# MCU.net
KiCad netlist of a schematic drawn in Altium Designer
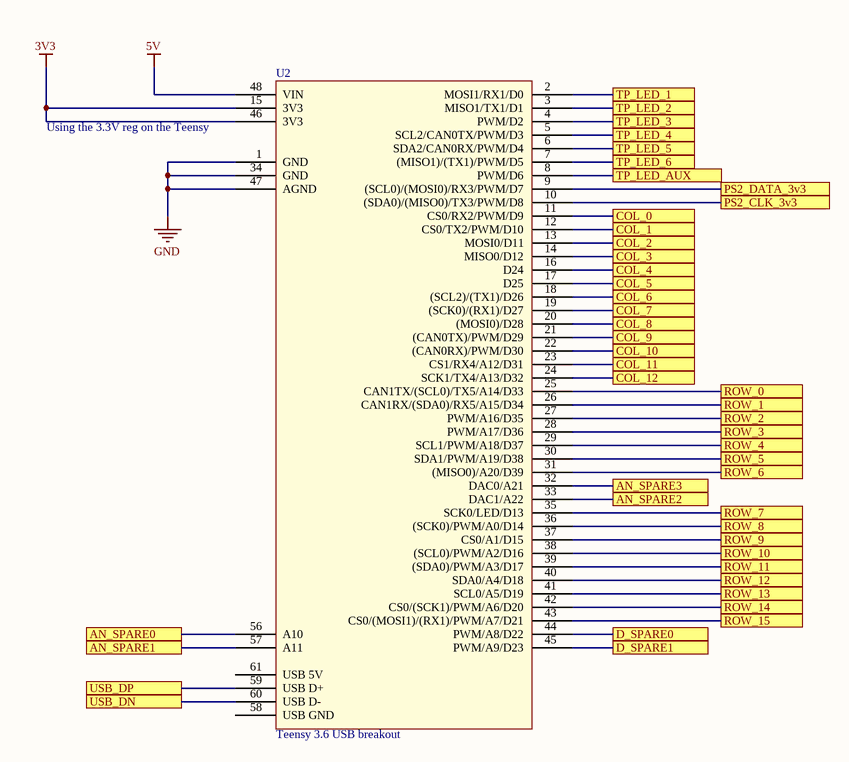
[diagram p0: MCU.SchDoc]

(export (version "E")
  (design (tool "Eeschema 10.0.6"))
  (components
    (comp (ref "U2")
      (value "Teensy 3.6 USB breakout")
      (footprint "Teensy 3.6 - USB Breakout")
      (libsource (lib "KBuchka-IntLib") (part "Teensy 3.6 USB breakout"))
    )
  )
  (nets
    (net (code "1") (name "/AN_SPARE0") (class "Default")
      (node (ref "U2") (pin "56") (pinfunction "A10_56") (pintype "passive"))
    )
    (net (code "2") (name "/AN_SPARE1") (class "Default")
      (node (ref "U2") (pin "57") (pinfunction "A11_57") (pintype "passive"))
    )
    (net (code "3") (name "/AN_SPARE2") (class "Default")
      (node (ref "U2") (pin "33") (pinfunction "DAC1/A22_33") (pintype "passive"))
    )
    (net (code "4") (name "/AN_SPARE3") (class "Default")
      (node (ref "U2") (pin "32") (pinfunction "DAC0/A21_32") (pintype "passive"))
    )
    (net (code "5") (name "/COL_0") (class "Default")
      (node (ref "U2") (pin "11") (pinfunction "CS0/RX2/PWM/D9_11") (pintype "passive"))
    )
    (net (code "6") (name "/COL_1") (class "Default")
      (node (ref "U2") (pin "12") (pinfunction "CS0/TX2/PWM/D10_12") (pintype "passive"))
    )
    (net (code "7") (name "/COL_2") (class "Default")
      (node (ref "U2") (pin "13") (pinfunction "MOSI0/D11_13") (pintype "passive"))
    )
    (net (code "8") (name "/COL_3") (class "Default")
      (node (ref "U2") (pin "14") (pinfunction "MISO0/D12_14") (pintype "passive"))
    )
    (net (code "9") (name "/COL_4") (class "Default")
      (node (ref "U2") (pin "16") (pinfunction "D24_16") (pintype "passive"))
    )
    (net (code "10") (name "/COL_5") (class "Default")
      (node (ref "U2") (pin "17") (pinfunction "D25_17") (pintype "passive"))
    )
    (net (code "11") (name "/COL_6") (class "Default")
      (node (ref "U2") (pin "18") (pinfunction "(SCL2)/(TX1)/D26_18") (pintype "passive"))
    )
    (net (code "12") (name "/COL_7") (class "Default")
      (node (ref "U2") (pin "19") (pinfunction "(SCK0)/(RX1)/D27_19") (pintype "passive"))
    )
    (net (code "13") (name "/COL_8") (class "Default")
      (node (ref "U2") (pin "20") (pinfunction "(MOSI0)/D28_20") (pintype "passive"))
    )
    (net (code "14") (name "/COL_9") (class "Default")
      (node (ref "U2") (pin "21") (pinfunction "(CAN0TX)/PWM/D29_21") (pintype "passive"))
    )
    (net (code "15") (name "/COL_10") (class "Default")
      (node (ref "U2") (pin "22") (pinfunction "(CAN0RX)/PWM/D30_22") (pintype "passive"))
    )
    (net (code "16") (name "/COL_11") (class "Default")
      (node (ref "U2") (pin "23") (pinfunction "CS1/RX4/A12/D31_23") (pintype "passive"))
    )
    (net (code "17") (name "/COL_12") (class "Default")
      (node (ref "U2") (pin "24") (pinfunction "SCK1/TX4/A13/D32_24") (pintype "passive"))
    )
    (net (code "18") (name "/D_SPARE0") (class "Default")
      (node (ref "U2") (pin "44") (pinfunction "PWM/A8/D22_44") (pintype "passive"))
    )
    (net (code "19") (name "/D_SPARE1") (class "Default")
      (node (ref "U2") (pin "45") (pinfunction "PWM/A9/D23_45") (pintype "passive"))
    )
    (net (code "20") (name "/PS2_CLK_3v3") (class "Default")
      (node (ref "U2") (pin "10") (pinfunction "(SDA0)/(MISO0)/TX3/PWM/D8_10") (pintype "passive"))
    )
    (net (code "21") (name "/PS2_DATA_3v3") (class "Default")
      (node (ref "U2") (pin "9") (pinfunction "(SCL0)/(MOSI0)/RX3/PWM/D7_9") (pintype "passive"))
    )
    (net (code "22") (name "/ROW_0") (class "Default")
      (node (ref "U2") (pin "25") (pinfunction "CAN1TX/(SCL0)/TX5/A14/D33_25") (pintype "passive"))
    )
    (net (code "23") (name "/ROW_1") (class "Default")
      (node (ref "U2") (pin "26") (pinfunction "CAN1RX/(SDA0)/RX5/A15/D34_26") (pintype "passive"))
    )
    (net (code "24") (name "/ROW_2") (class "Default")
      (node (ref "U2") (pin "27") (pinfunction "PWM/A16/D35_27") (pintype "passive"))
    )
    (net (code "25") (name "/ROW_3") (class "Default")
      (node (ref "U2") (pin "28") (pinfunction "PWM/A17/D36_28") (pintype "passive"))
    )
    (net (code "26") (name "/ROW_4") (class "Default")
      (node (ref "U2") (pin "29") (pinfunction "SCL1/PWM/A18/D37_29") (pintype "passive"))
    )
    (net (code "27") (name "/ROW_5") (class "Default")
      (node (ref "U2") (pin "30") (pinfunction "SDA1/PWM/A19/D38_30") (pintype "passive"))
    )
    (net (code "28") (name "/ROW_6") (class "Default")
      (node (ref "U2") (pin "31") (pinfunction "(MISO0)/A20/D39_31") (pintype "passive"))
    )
    (net (code "29") (name "/ROW_7") (class "Default")
      (node (ref "U2") (pin "35") (pinfunction "SCK0/LED/D13_35") (pintype "passive"))
    )
    (net (code "30") (name "/ROW_8") (class "Default")
      (node (ref "U2") (pin "36") (pinfunction "(SCK0)/PWM/A0/D14_36") (pintype "passive"))
    )
    (net (code "31") (name "/ROW_9") (class "Default")
      (node (ref "U2") (pin "37") (pinfunction "CS0/A1/D15_37") (pintype "passive"))
    )
    (net (code "32") (name "/ROW_10") (class "Default")
      (node (ref "U2") (pin "38") (pinfunction "(SCL0)/PWM/A2/D16_38") (pintype "passive"))
    )
    (net (code "33") (name "/ROW_11") (class "Default")
      (node (ref "U2") (pin "39") (pinfunction "(SDA0)/PWM/A3/D17_39") (pintype "passive"))
    )
    (net (code "34") (name "/ROW_12") (class "Default")
      (node (ref "U2") (pin "40") (pinfunction "SDA0/A4/D18_40") (pintype "passive"))
    )
    (net (code "35") (name "/ROW_13") (class "Default")
      (node (ref "U2") (pin "41") (pinfunction "SCL0/A5/D19_41") (pintype "passive"))
    )
    (net (code "36") (name "/ROW_14") (class "Default")
      (node (ref "U2") (pin "42") (pinfunction "CS0/(SCK1)/PWM/A6/D20_42") (pintype "passive"))
    )
    (net (code "37") (name "/ROW_15") (class "Default")
      (node (ref "U2") (pin "43") (pinfunction "CS0/(MOSI1)/(RX1)/PWM/A7/D21_43") (pintype "passive"))
    )
    (net (code "38") (name "/TP_LED_1") (class "Default")
      (node (ref "U2") (pin "2") (pinfunction "MOSI1/RX1/D0_2") (pintype "passive"))
    )
    (net (code "39") (name "/TP_LED_2") (class "Default")
      (node (ref "U2") (pin "3") (pinfunction "MISO1/TX1/D1_3") (pintype "passive"))
    )
    (net (code "40") (name "/TP_LED_3") (class "Default")
      (node (ref "U2") (pin "4") (pinfunction "PWM/D2_4") (pintype "passive"))
    )
    (net (code "41") (name "/TP_LED_4") (class "Default")
      (node (ref "U2") (pin "5") (pinfunction "SCL2/CAN0TX/PWM/D3_5") (pintype "passive"))
    )
    (net (code "42") (name "/TP_LED_5") (class "Default")
      (node (ref "U2") (pin "6") (pinfunction "SDA2/CAN0RX/PWM/D4_6") (pintype "passive"))
    )
    (net (code "43") (name "/TP_LED_6") (class "Default")
      (node (ref "U2") (pin "7") (pinfunction "(MISO1)/(TX1)/PWM/D5_7") (pintype "passive"))
    )
    (net (code "44") (name "/TP_LED_AUX") (class "Default")
      (node (ref "U2") (pin "8") (pinfunction "PWM/D6_8") (pintype "passive"))
    )
    (net (code "45") (name "/USB_DN") (class "Default")
      (node (ref "U2") (pin "60") (pinfunction "USB_D-_60") (pintype "passive"))
    )
    (net (code "46") (name "/USB_DP") (class "Default")
      (node (ref "U2") (pin "59") (pinfunction "USB_D+_59") (pintype "passive"))
    )
    (net (code "47") (name "3V3") (class "Default")
      (node (ref "U2") (pin "15") (pinfunction "3V3_15") (pintype "passive"))
      (node (ref "U2") (pin "46") (pinfunction "3V3_46") (pintype "passive"))
    )
    (net (code "48") (name "5V") (class "Default")
      (node (ref "U2") (pin "48") (pinfunction "VIN_48") (pintype "passive"))
    )
    (net (code "49") (name "GND") (class "Default")
      (node (ref "U2") (pin "1") (pinfunction "GND_1") (pintype "passive"))
      (node (ref "U2") (pin "34") (pinfunction "GND_34") (pintype "passive"))
      (node (ref "U2") (pin "47") (pinfunction "AGND_47") (pintype "passive"))
    )
    (net (code "50") (name "unconnected-(U2-USB_5V-Pad61)") (class "Default")
      (node (ref "U2") (pin "61") (pinfunction "USB_5V_61") (pintype "passive"))
    )
    (net (code "51") (name "unconnected-(U2-USB_GND-Pad58)") (class "Default")
      (node (ref "U2") (pin "58") (pinfunction "USB_GND_58") (pintype "passive"))
    )
  )
)
